# ADC088S022_VAR.net
KiCad netlist of a schematic drawn in Altium Designer
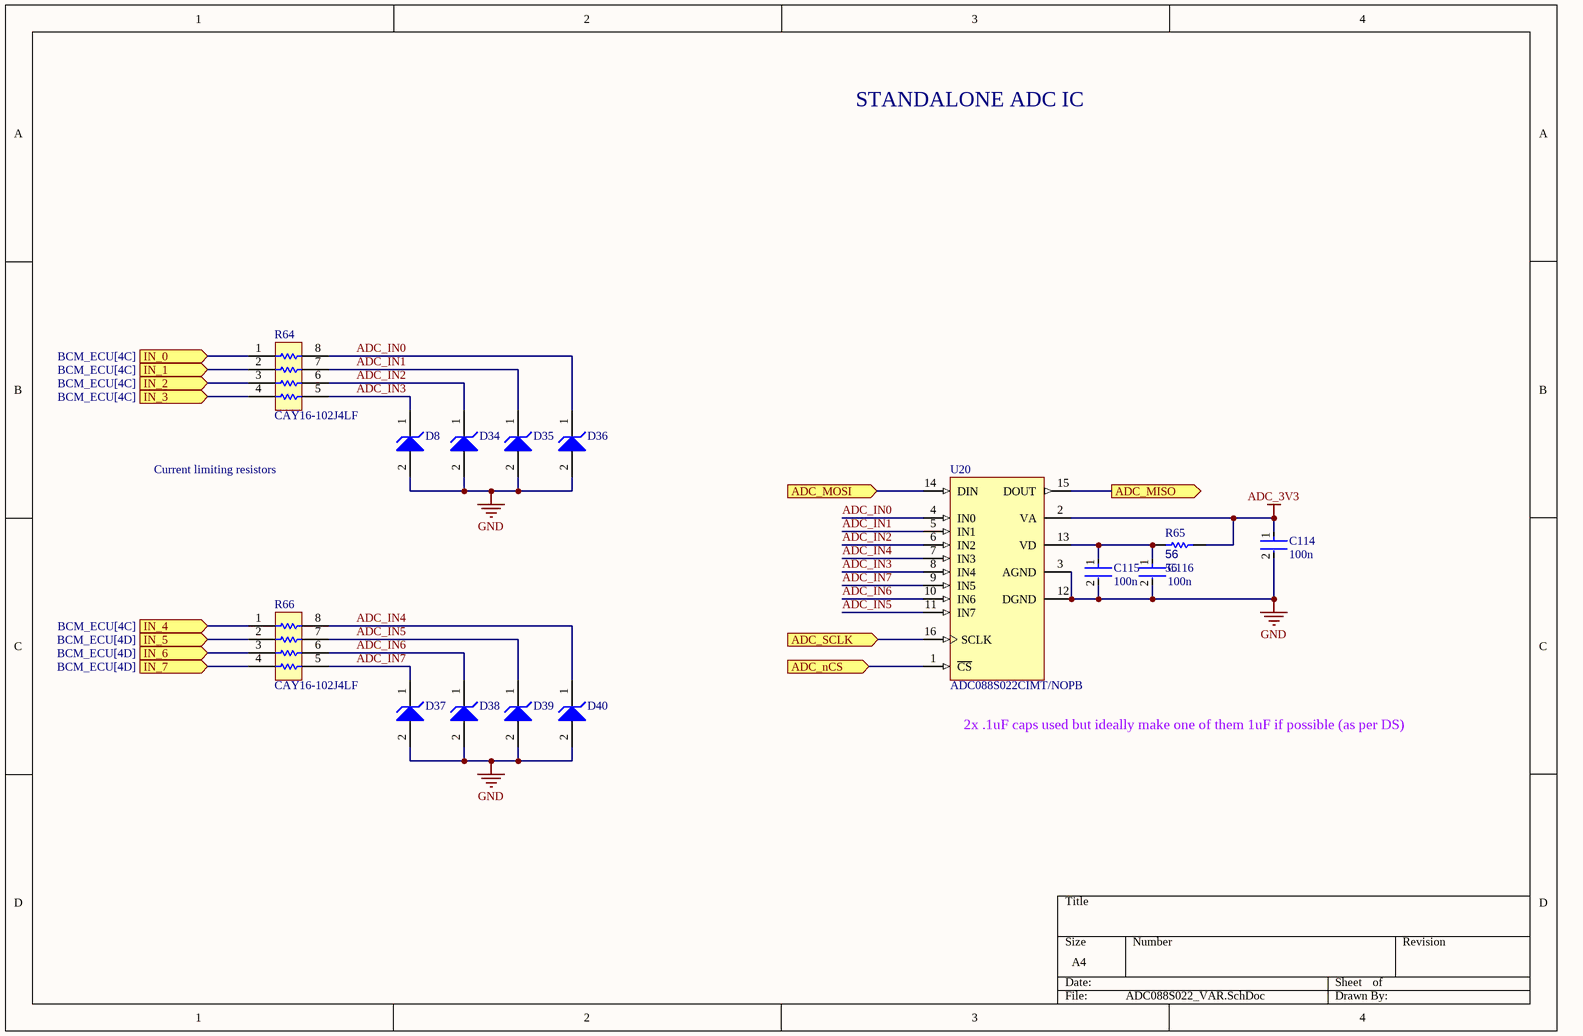
[diagram p0: ADC088S022_VAR.SchDoc]

(export (version "E")
  (design (tool "Eeschema 10.0.6"))
  (components
    (comp (ref "C114")
      (value "100n")
      (footprint "FP-0402-L_1_0_0_05-W_0_5-IPC_A")
      (description "LARGE PADS, 0402 CAP, CHANGE COMMENT TO MATCH REAL P/N")
      (libsource (lib "Space Concordia") (part "b4654b650e69147ec39a6b967a45e02"))
    )
    (comp (ref "C115")
      (value "100n")
      (footprint "FP-0402-L_1_0_0_05-W_0_5-IPC_A")
      (description "LARGE PADS, 0402 CAP, CHANGE COMMENT TO MATCH REAL P/N")
      (libsource (lib "Space Concordia") (part "b4654b650e69147ec39a6b967a45e02"))
    )
    (comp (ref "C116")
      (value "100n")
      (footprint "FP-0402-L_1_0_0_05-W_0_5-IPC_A")
      (description "LARGE PADS, 0402 CAP, CHANGE COMMENT TO MATCH REAL P/N")
      (libsource (lib "Space Concordia") (part "b4654b650e69147ec39a6b967a45e02"))
    )
    (comp (ref "D8")
      (value "MM5Z3V3T1G")
      (footprint "ONSC-SOD-523-2-502-01_V")
      (description "Zener Voltage Regulator, 500 mW, 2-Pin SOD-523, Pb-Free, Tape and Reel")
      (fields (field (name "MANUFACTURER") "On Semiconductor"))
      (libsource (lib "Altium Content Vault") (part "ONSC-K1A2-2"))
    )
    (comp (ref "D34")
      (value "MM5Z3V3T1G")
      (footprint "ONSC-SOD-523-2-502-01_V")
      (description "Zener Voltage Regulator, 500 mW, 2-Pin SOD-523, Pb-Free, Tape and Reel")
      (fields (field (name "MANUFACTURER") "On Semiconductor"))
      (libsource (lib "Altium Content Vault") (part "ONSC-K1A2-2"))
    )
    (comp (ref "D35")
      (value "MM5Z3V3T1G")
      (footprint "ONSC-SOD-523-2-502-01_V")
      (description "Zener Voltage Regulator, 500 mW, 2-Pin SOD-523, Pb-Free, Tape and Reel")
      (fields (field (name "MANUFACTURER") "On Semiconductor"))
      (libsource (lib "Altium Content Vault") (part "ONSC-K1A2-2"))
    )
    (comp (ref "D36")
      (value "MM5Z3V3T1G")
      (footprint "ONSC-SOD-523-2-502-01_V")
      (description "Zener Voltage Regulator, 500 mW, 2-Pin SOD-523, Pb-Free, Tape and Reel")
      (fields (field (name "MANUFACTURER") "On Semiconductor"))
      (libsource (lib "Altium Content Vault") (part "ONSC-K1A2-2"))
    )
    (comp (ref "D37")
      (value "MM5Z3V3T1G")
      (footprint "ONSC-SOD-523-2-502-01_V")
      (description "Zener Voltage Regulator, 500 mW, 2-Pin SOD-523, Pb-Free, Tape and Reel")
      (fields (field (name "MANUFACTURER") "On Semiconductor"))
      (libsource (lib "Altium Content Vault") (part "ONSC-K1A2-2"))
    )
    (comp (ref "D38")
      (value "MM5Z3V3T1G")
      (footprint "ONSC-SOD-523-2-502-01_V")
      (description "Zener Voltage Regulator, 500 mW, 2-Pin SOD-523, Pb-Free, Tape and Reel")
      (fields (field (name "MANUFACTURER") "On Semiconductor"))
      (libsource (lib "Altium Content Vault") (part "ONSC-K1A2-2"))
    )
    (comp (ref "D39")
      (value "MM5Z3V3T1G")
      (footprint "ONSC-SOD-523-2-502-01_V")
      (description "Zener Voltage Regulator, 500 mW, 2-Pin SOD-523, Pb-Free, Tape and Reel")
      (fields (field (name "MANUFACTURER") "On Semiconductor"))
      (libsource (lib "Altium Content Vault") (part "ONSC-K1A2-2"))
    )
    (comp (ref "D40")
      (value "MM5Z3V3T1G")
      (footprint "ONSC-SOD-523-2-502-01_V")
      (description "Zener Voltage Regulator, 500 mW, 2-Pin SOD-523, Pb-Free, Tape and Reel")
      (fields (field (name "MANUFACTURER") "On Semiconductor"))
      (libsource (lib "Altium Content Vault") (part "ONSC-K1A2-2"))
    )
    (comp (ref "R64")
      (value "CAY16-102J4LF")
      (footprint "BOUR-CAY16-J4_V")
      (description "Chip Resistor Array, 1 KOhm, +/- 5%, 62.5 mW, -55 to 125 degC, 8-Pin SMD, RoHS, Tape and Reel")
      (fields (field (name "TOLERANCE") "1%"))
      (libsource (lib "Altium Content Vault") (part "RES-P-8"))
    )
    (comp (ref "R65")
      (value "56")
      (footprint "R0603B")
      (description "Resistor")
      (fields (field (name "ALTIUM_VALUE") "56"))
      (libsource (lib "Space Concordia") (part "Resistor"))
    )
    (comp (ref "R66")
      (value "CAY16-102J4LF")
      (footprint "BOUR-CAY16-J4_V")
      (description "Chip Resistor Array, 1 KOhm, +/- 5%, 62.5 mW, -55 to 125 degC, 8-Pin SMD, RoHS, Tape and Reel")
      (fields (field (name "TOLERANCE") "1%"))
      (libsource (lib "Altium Content Vault") (part "RES-P-8"))
    )
    (comp (ref "U20")
      (value "ADC088S022CIMT/NOPB")
      (footprint "MTC16_L")
      (description "8-Channel, 50 kSPS to 200 kSPS, 8-Bit A/D Converter, 16-pin TSSOP, Pb-Free")
      (fields (field (name "MANUFACTURER") "National Semiconductor"))
      (libsource (lib "Altium Content Vault") (part "CON-ADC-ADC108S052CIMT"))
    )
  )
  (nets
    (net (code "1") (name "/ADC_IN0") (class "Default")
      (node (ref "D36") (pin "1") (pinfunction "K_1") (pintype "passive"))
      (node (ref "R64") (pin "8") (pinfunction "8_8") (pintype "passive"))
      (node (ref "U20") (pin "4") (pinfunction "IN0_4") (pintype "input"))
    )
    (net (code "2") (name "/ADC_IN1") (class "Default")
      (node (ref "D35") (pin "1") (pinfunction "K_1") (pintype "passive"))
      (node (ref "R64") (pin "7") (pinfunction "7_7") (pintype "passive"))
      (node (ref "U20") (pin "5") (pinfunction "IN1_5") (pintype "input"))
    )
    (net (code "3") (name "/ADC_IN2") (class "Default")
      (node (ref "D34") (pin "1") (pinfunction "K_1") (pintype "passive"))
      (node (ref "R64") (pin "6") (pinfunction "6_6") (pintype "passive"))
      (node (ref "U20") (pin "6") (pinfunction "IN2_6") (pintype "input"))
    )
    (net (code "4") (name "/ADC_IN3") (class "Default")
      (node (ref "D8") (pin "1") (pinfunction "K_1") (pintype "passive"))
      (node (ref "R64") (pin "5") (pinfunction "5_5") (pintype "passive"))
      (node (ref "U20") (pin "8") (pinfunction "IN4_8") (pintype "input"))
    )
    (net (code "5") (name "/ADC_IN4") (class "Default")
      (node (ref "D40") (pin "1") (pinfunction "K_1") (pintype "passive"))
      (node (ref "R66") (pin "8") (pinfunction "8_8") (pintype "passive"))
      (node (ref "U20") (pin "7") (pinfunction "IN3_7") (pintype "input"))
    )
    (net (code "6") (name "/ADC_IN5") (class "Default")
      (node (ref "D39") (pin "1") (pinfunction "K_1") (pintype "passive"))
      (node (ref "R66") (pin "7") (pinfunction "7_7") (pintype "passive"))
      (node (ref "U20") (pin "11") (pinfunction "IN7_11") (pintype "input"))
    )
    (net (code "7") (name "/ADC_IN6") (class "Default")
      (node (ref "D38") (pin "1") (pinfunction "K_1") (pintype "passive"))
      (node (ref "R66") (pin "6") (pinfunction "6_6") (pintype "passive"))
      (node (ref "U20") (pin "10") (pinfunction "IN6_10") (pintype "input"))
    )
    (net (code "8") (name "/ADC_IN7") (class "Default")
      (node (ref "D37") (pin "1") (pinfunction "K_1") (pintype "passive"))
      (node (ref "R66") (pin "5") (pinfunction "5_5") (pintype "passive"))
      (node (ref "U20") (pin "9") (pinfunction "IN5_9") (pintype "input"))
    )
    (net (code "9") (name "/ADC_MISO") (class "Default")
      (node (ref "U20") (pin "15") (pinfunction "DOUT_15") (pintype "output"))
    )
    (net (code "10") (name "/ADC_MOSI") (class "Default")
      (node (ref "U20") (pin "14") (pinfunction "DIN_14") (pintype "input"))
    )
    (net (code "11") (name "/ADC_SCLK") (class "Default")
      (node (ref "U20") (pin "16") (pinfunction "SCLK_16") (pintype "input"))
    )
    (net (code "12") (name "/ADC_nCS") (class "Default")
      (node (ref "U20") (pin "1") (pinfunction "~{CS}_1") (pintype "input"))
    )
    (net (code "13") (name "/IN_0") (class "Default")
      (node (ref "R64") (pin "1") (pinfunction "1_1") (pintype "passive"))
    )
    (net (code "14") (name "/IN_1") (class "Default")
      (node (ref "R64") (pin "2") (pinfunction "2_2") (pintype "passive"))
    )
    (net (code "15") (name "/IN_2") (class "Default")
      (node (ref "R64") (pin "3") (pinfunction "3_3") (pintype "passive"))
    )
    (net (code "16") (name "/IN_3") (class "Default")
      (node (ref "R64") (pin "4") (pinfunction "4_4") (pintype "passive"))
    )
    (net (code "17") (name "/IN_4") (class "Default")
      (node (ref "R66") (pin "1") (pinfunction "1_1") (pintype "passive"))
    )
    (net (code "18") (name "/IN_5") (class "Default")
      (node (ref "R66") (pin "2") (pinfunction "2_2") (pintype "passive"))
    )
    (net (code "19") (name "/IN_6") (class "Default")
      (node (ref "R66") (pin "3") (pinfunction "3_3") (pintype "passive"))
    )
    (net (code "20") (name "/IN_7") (class "Default")
      (node (ref "R66") (pin "4") (pinfunction "4_4") (pintype "passive"))
    )
    (net (code "21") (name "ADC_3V3") (class "Default")
      (node (ref "C114") (pin "1") (pinfunction "1_1") (pintype "passive"))
      (node (ref "R65") (pin "1") (pinfunction "1_1") (pintype "passive"))
      (node (ref "U20") (pin "2") (pinfunction "VA_2") (pintype "power_in"))
    )
    (net (code "22") (name "GND") (class "Default")
      (node (ref "C114") (pin "2") (pinfunction "2_2") (pintype "passive"))
      (node (ref "C115") (pin "2") (pinfunction "2_2") (pintype "passive"))
      (node (ref "C116") (pin "2") (pinfunction "2_2") (pintype "passive"))
      (node (ref "D34") (pin "2") (pinfunction "A_2") (pintype "passive"))
      (node (ref "D35") (pin "2") (pinfunction "A_2") (pintype "passive"))
      (node (ref "D36") (pin "2") (pinfunction "A_2") (pintype "passive"))
      (node (ref "D37") (pin "2") (pinfunction "A_2") (pintype "passive"))
      (node (ref "D38") (pin "2") (pinfunction "A_2") (pintype "passive"))
      (node (ref "D39") (pin "2") (pinfunction "A_2") (pintype "passive"))
      (node (ref "D40") (pin "2") (pinfunction "A_2") (pintype "passive"))
      (node (ref "D8") (pin "2") (pinfunction "A_2") (pintype "passive"))
      (node (ref "U20") (pin "12") (pinfunction "DGND_12") (pintype "power_in"))
      (node (ref "U20") (pin "3") (pinfunction "AGND_3") (pintype "power_in"))
    )
    (net (code "23") (name "Net-(U20-VD)") (class "Default")
      (node (ref "C115") (pin "1") (pinfunction "1_1") (pintype "passive"))
      (node (ref "C116") (pin "1") (pinfunction "1_1") (pintype "passive"))
      (node (ref "R65") (pin "2") (pinfunction "2_2") (pintype "passive"))
      (node (ref "U20") (pin "13") (pinfunction "VD_13") (pintype "power_in"))
    )
  )
)
